# DragonShield.net
KiCad netlist of a schematic drawn in EAGLE
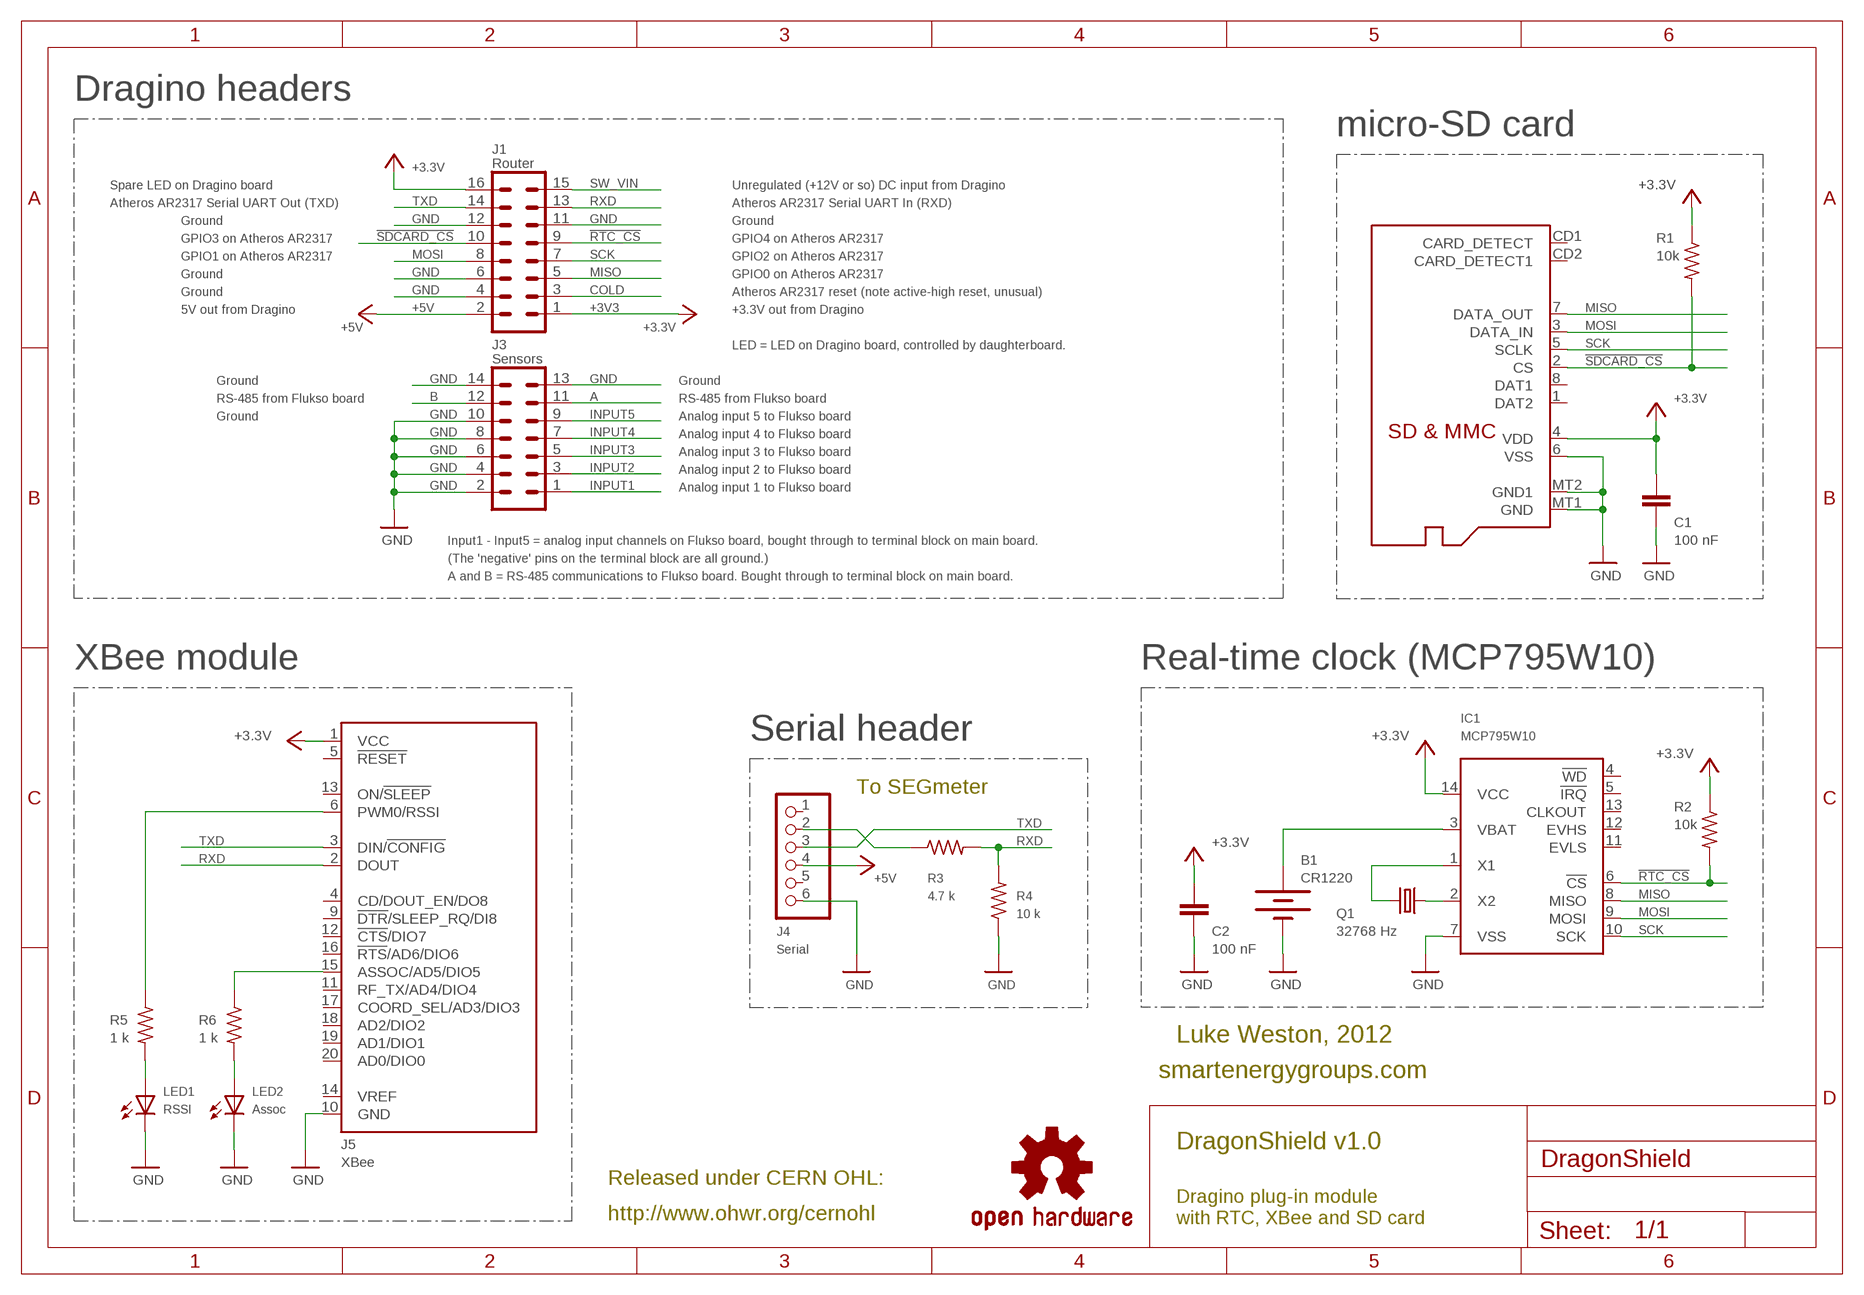
[diagram p0: schematic, sheet 1]

(export (version "E")
  (design (tool "Eeschema 10.0.6"))
  (components
    (comp (ref "B1")
      (value "CR1220")
      (footprint "eagle-import:BATTCON_12MM")
      (libsource (lib "eagle-import") (part "BATTERY12MM"))
    )
    (comp (ref "C1")
      (value "100 nF")
      (footprint "eagle-import:C0805K")
      (libsource (lib "eagle-import") (part "C-EUC0805K"))
    )
    (comp (ref "C2")
      (value "100 nF")
      (footprint "eagle-import:C0805K")
      (libsource (lib "eagle-import") (part "C-EUC0805K"))
    )
    (comp (ref "IC1")
      (value "MCP795W10")
      (footprint "eagle-import:SOIC14")
      (libsource (lib "eagle-import") (part "MCP795W10SO"))
    )
    (comp (ref "J1")
      (value "Router")
      (footprint "eagle-import:MA08-2")
      (libsource (lib "eagle-import") (part "MA08-2"))
    )
    (comp (ref "J2")
      (value "MICROSD")
      (footprint "eagle-import:MICROSD")
      (libsource (lib "eagle-import") (part "MICROSD"))
    )
    (comp (ref "J3")
      (value "Sensors")
      (footprint "eagle-import:MA07-2")
      (libsource (lib "eagle-import") (part "MA07-2"))
    )
    (comp (ref "J4")
      (value "Serial")
      (footprint "eagle-import:1X06")
      (libsource (lib "eagle-import") (part "PINHD-1X6"))
    )
    (comp (ref "J5")
      (value "XBee")
      (footprint "eagle-import:XBEE-PRO")
      (fields (field (name "MPN") "XBP24-AWI-001"))
      (libsource (lib "eagle-import") (part "XBEE-PRO"))
    )
    (comp (ref "LED1")
      (value "RSSI")
      (footprint "eagle-import:LED-0805-LARGE")
      (libsource (lib "eagle-import") (part "LED0805-LARGE"))
    )
    (comp (ref "LED2")
      (value "Assoc")
      (footprint "eagle-import:LED-0805-LARGE")
      (libsource (lib "eagle-import") (part "LED0805-LARGE"))
    )
    (comp (ref "Q1")
      (value "32768 Hz")
      (footprint "eagle-import:TC26H")
      (libsource (lib "eagle-import") (part "CRYSTALTC26H"))
    )
    (comp (ref "R1")
      (value "10k")
      (footprint "eagle-import:M0805")
      (libsource (lib "eagle-import") (part "R-US_M0805"))
    )
    (comp (ref "R2")
      (value "10k")
      (footprint "eagle-import:M0805")
      (libsource (lib "eagle-import") (part "R-US_M0805"))
    )
    (comp (ref "R3")
      (value "4.7 k")
      (footprint "eagle-import:M0805")
      (libsource (lib "eagle-import") (part "R-US_M0805"))
    )
    (comp (ref "R4")
      (value "10 k")
      (footprint "eagle-import:M0805")
      (libsource (lib "eagle-import") (part "R-US_M0805"))
    )
    (comp (ref "R5")
      (value "1 k")
      (footprint "eagle-import:M0805")
      (libsource (lib "eagle-import") (part "R-US_M0805"))
    )
    (comp (ref "R6")
      (value "1 k")
      (footprint "eagle-import:M0805")
      (libsource (lib "eagle-import") (part "R-US_M0805"))
    )
    (comp (ref "U$")
      (value "OSHW-LOGOS")
      (footprint "eagle-import:OSHW-LOGO-S")
      (libsource (lib "eagle-import") (part "OSHW-LOGOS"))
    )
  )
  (nets
    (net (code "1") (name "+3.3V") (class "Default")
      (node (ref "C1") (pin "2") (pinfunction "2_2") (pintype "passive"))
      (node (ref "C2") (pin "2") (pinfunction "2_2") (pintype "passive"))
      (node (ref "IC1") (pin "14") (pinfunction "VCC_14") (pintype "bidirectional"))
      (node (ref "J1") (pin "1") (pinfunction "1_1") (pintype "passive"))
      (node (ref "J1") (pin "16") (pinfunction "16_16") (pintype "passive"))
      (node (ref "J2") (pin "4") (pinfunction "VDD_4") (pintype "power_in"))
      (node (ref "J5") (pin "1") (pinfunction "VCC_1") (pintype "power_in"))
      (node (ref "R1") (pin "1") (pinfunction "1_1") (pintype "passive"))
      (node (ref "R2") (pin "1") (pinfunction "1_1") (pintype "passive"))
    )
    (net (code "2") (name "+5V") (class "Default")
      (node (ref "J1") (pin "2") (pinfunction "2_2") (pintype "passive"))
      (node (ref "J4") (pin "4") (pinfunction "4_4") (pintype "passive"))
    )
    (net (code "3") (name "/A") (class "Default")
      (node (ref "J3") (pin "11") (pinfunction "11_11") (pintype "passive"))
    )
    (net (code "4") (name "/B") (class "Default")
      (node (ref "J3") (pin "12") (pinfunction "12_12") (pintype "passive"))
    )
    (net (code "5") (name "/COLD") (class "Default")
      (node (ref "J1") (pin "3") (pinfunction "3_3") (pintype "passive"))
    )
    (net (code "6") (name "/INPUT1") (class "Default")
      (node (ref "J3") (pin "1") (pinfunction "1_1") (pintype "passive"))
    )
    (net (code "7") (name "/INPUT2") (class "Default")
      (node (ref "J3") (pin "3") (pinfunction "3_3") (pintype "passive"))
    )
    (net (code "8") (name "/INPUT3") (class "Default")
      (node (ref "J3") (pin "5") (pinfunction "5_5") (pintype "passive"))
    )
    (net (code "9") (name "/INPUT4") (class "Default")
      (node (ref "J3") (pin "7") (pinfunction "7_7") (pintype "passive"))
    )
    (net (code "10") (name "/INPUT5") (class "Default")
      (node (ref "J3") (pin "9") (pinfunction "9_9") (pintype "passive"))
    )
    (net (code "11") (name "/MISO") (class "Default")
      (node (ref "IC1") (pin "8") (pinfunction "MISO_8") (pintype "bidirectional"))
      (node (ref "J1") (pin "5") (pinfunction "5_5") (pintype "passive"))
      (node (ref "J2") (pin "7") (pinfunction "DATA_OUT_7") (pintype "output"))
    )
    (net (code "12") (name "/MOSI") (class "Default")
      (node (ref "IC1") (pin "9") (pinfunction "MOSI_9") (pintype "bidirectional"))
      (node (ref "J1") (pin "8") (pinfunction "8_8") (pintype "passive"))
      (node (ref "J2") (pin "3") (pinfunction "DATA_IN_3") (pintype "input"))
    )
    (net (code "13") (name "/RXD") (class "Default")
      (node (ref "J1") (pin "13") (pinfunction "13_13") (pintype "passive"))
      (node (ref "J5") (pin "2") (pinfunction "DOUT_2") (pintype "output"))
      (node (ref "R3") (pin "2") (pinfunction "2_2") (pintype "passive"))
      (node (ref "R4") (pin "2") (pinfunction "2_2") (pintype "passive"))
    )
    (net (code "14") (name "/SCK") (class "Default")
      (node (ref "IC1") (pin "10") (pinfunction "SCK_10") (pintype "bidirectional"))
      (node (ref "J1") (pin "7") (pinfunction "7_7") (pintype "passive"))
      (node (ref "J2") (pin "5") (pinfunction "SCLK_5") (pintype "input"))
    )
    (net (code "15") (name "/SW_VIN") (class "Default")
      (node (ref "J1") (pin "15") (pinfunction "15_15") (pintype "passive"))
    )
    (net (code "16") (name "/TXD") (class "Default")
      (node (ref "J1") (pin "14") (pinfunction "14_14") (pintype "passive"))
      (node (ref "J4") (pin "3") (pinfunction "3_3") (pintype "passive"))
      (node (ref "J5") (pin "3") (pinfunction "DIN/~{CONFIG}_3") (pintype "input"))
    )
    (net (code "17") (name "/~{RTC_CS}") (class "Default")
      (node (ref "IC1") (pin "6") (pinfunction "~{CS}_6") (pintype "bidirectional"))
      (node (ref "J1") (pin "9") (pinfunction "9_9") (pintype "passive"))
      (node (ref "R2") (pin "2") (pinfunction "2_2") (pintype "passive"))
    )
    (net (code "18") (name "/~{SDCARD_CS}") (class "Default")
      (node (ref "J1") (pin "10") (pinfunction "10_10") (pintype "passive"))
      (node (ref "J2") (pin "2") (pinfunction "CS_2") (pintype "input"))
      (node (ref "R1") (pin "2") (pinfunction "2_2") (pintype "passive"))
    )
    (net (code "19") (name "GND") (class "Default")
      (node (ref "B1") (pin "GND") (pinfunction "-_GND") (pintype "power_in"))
      (node (ref "C1") (pin "1") (pinfunction "1_1") (pintype "passive"))
      (node (ref "C2") (pin "1") (pinfunction "1_1") (pintype "passive"))
      (node (ref "IC1") (pin "7") (pinfunction "VSS_7") (pintype "bidirectional"))
      (node (ref "J1") (pin "11") (pinfunction "11_11") (pintype "passive"))
      (node (ref "J1") (pin "12") (pinfunction "12_12") (pintype "passive"))
      (node (ref "J1") (pin "4") (pinfunction "4_4") (pintype "passive"))
      (node (ref "J1") (pin "6") (pinfunction "6_6") (pintype "passive"))
      (node (ref "J2") (pin "6") (pinfunction "VSS_6") (pintype "power_in"))
      (node (ref "J2") (pin "MT1") (pinfunction "GND_MT1") (pintype "power_in"))
      (node (ref "J2") (pin "MT2") (pinfunction "GND1_MT2") (pintype "power_in"))
      (node (ref "J3") (pin "10") (pinfunction "10_10") (pintype "passive"))
      (node (ref "J3") (pin "13") (pinfunction "13_13") (pintype "passive"))
      (node (ref "J3") (pin "14") (pinfunction "14_14") (pintype "passive"))
      (node (ref "J3") (pin "2") (pinfunction "2_2") (pintype "passive"))
      (node (ref "J3") (pin "4") (pinfunction "4_4") (pintype "passive"))
      (node (ref "J3") (pin "6") (pinfunction "6_6") (pintype "passive"))
      (node (ref "J3") (pin "8") (pinfunction "8_8") (pintype "passive"))
      (node (ref "J4") (pin "6") (pinfunction "6_6") (pintype "passive"))
      (node (ref "J5") (pin "10") (pinfunction "GND_10") (pintype "power_in"))
      (node (ref "LED1") (pin "C") (pinfunction "C_C") (pintype "passive"))
      (node (ref "LED2") (pin "C") (pinfunction "C_C") (pintype "passive"))
      (node (ref "R4") (pin "1") (pinfunction "1_1") (pintype "passive"))
    )
    (net (code "20") (name "Net-(B1-+)") (class "Default")
      (node (ref "B1") (pin "PWR@1") (pinfunction "+_PWR@1") (pintype "power_in"))
      (node (ref "IC1") (pin "3") (pinfunction "VBAT_3") (pintype "bidirectional"))
    )
    (net (code "21") (name "Net-(IC1-X1)") (class "Default")
      (node (ref "IC1") (pin "1") (pinfunction "X1_1") (pintype "bidirectional"))
      (node (ref "Q1") (pin "2") (pinfunction "2_2") (pintype "passive"))
    )
    (net (code "22") (name "Net-(IC1-X2)") (class "Default")
      (node (ref "IC1") (pin "2") (pinfunction "X2_2") (pintype "bidirectional"))
      (node (ref "Q1") (pin "1") (pinfunction "1_1") (pintype "passive"))
    )
    (net (code "23") (name "Net-(J4-Pad2)") (class "Default")
      (node (ref "J4") (pin "2") (pinfunction "2_2") (pintype "passive"))
      (node (ref "R3") (pin "1") (pinfunction "1_1") (pintype "passive"))
    )
    (net (code "24") (name "Net-(J5-ASSOC{slash}AD5{slash}DIO5)") (class "Default")
      (node (ref "J5") (pin "15") (pinfunction "ASSOC/AD5/DIO5_15") (pintype "bidirectional"))
      (node (ref "R6") (pin "1") (pinfunction "1_1") (pintype "passive"))
    )
    (net (code "25") (name "Net-(J5-PWM0{slash}RSSI)") (class "Default")
      (node (ref "J5") (pin "6") (pinfunction "PWM0/RSSI_6") (pintype "output"))
      (node (ref "R5") (pin "1") (pinfunction "1_1") (pintype "passive"))
    )
    (net (code "26") (name "Net-(LED1-PadA)") (class "Default")
      (node (ref "LED1") (pin "A") (pinfunction "A_A") (pintype "passive"))
      (node (ref "R5") (pin "2") (pinfunction "2_2") (pintype "passive"))
    )
    (net (code "27") (name "Net-(LED2-PadA)") (class "Default")
      (node (ref "LED2") (pin "A") (pinfunction "A_A") (pintype "passive"))
      (node (ref "R6") (pin "2") (pinfunction "2_2") (pintype "passive"))
    )
    (net (code "28") (name "unconnected-(IC1-CLKOUT-Pad13)") (class "Default")
      (node (ref "IC1") (pin "13") (pinfunction "CLKOUT_13") (pintype "bidirectional"))
    )
    (net (code "29") (name "unconnected-(IC1-EVHS-Pad12)") (class "Default")
      (node (ref "IC1") (pin "12") (pinfunction "EVHS_12") (pintype "bidirectional"))
    )
    (net (code "30") (name "unconnected-(IC1-EVLS-Pad11)") (class "Default")
      (node (ref "IC1") (pin "11") (pinfunction "EVLS_11") (pintype "bidirectional"))
    )
    (net (code "31") (name "unconnected-(IC1-~{IRQ}-Pad5)") (class "Default")
      (node (ref "IC1") (pin "5") (pinfunction "~{IRQ}_5") (pintype "bidirectional"))
    )
    (net (code "32") (name "unconnected-(IC1-~{WD}-Pad4)") (class "Default")
      (node (ref "IC1") (pin "4") (pinfunction "~{WD}_4") (pintype "bidirectional"))
    )
    (net (code "33") (name "unconnected-(J2-CARD_DETECT-PadCD1)") (class "Default")
      (node (ref "J2") (pin "CD1") (pinfunction "CARD_DETECT_CD1") (pintype "passive"))
    )
    (net (code "34") (name "unconnected-(J2-CARD_DETECT1-PadCD2)") (class "Default")
      (node (ref "J2") (pin "CD2") (pinfunction "CARD_DETECT1_CD2") (pintype "passive"))
    )
    (net (code "35") (name "unconnected-(J2-DAT1-Pad8)") (class "Default")
      (node (ref "J2") (pin "8") (pinfunction "DAT1_8") (pintype "bidirectional"))
    )
    (net (code "36") (name "unconnected-(J2-DAT2-Pad1)") (class "Default")
      (node (ref "J2") (pin "1") (pinfunction "DAT2_1") (pintype "bidirectional"))
    )
    (net (code "37") (name "unconnected-(J4-Pad1)") (class "Default")
      (node (ref "J4") (pin "1") (pinfunction "1_1") (pintype "passive"))
    )
    (net (code "38") (name "unconnected-(J4-Pad5)") (class "Default")
      (node (ref "J4") (pin "5") (pinfunction "5_5") (pintype "passive"))
    )
    (net (code "39") (name "unconnected-(J5-AD0{slash}DIO0-Pad20)") (class "Default")
      (node (ref "J5") (pin "20") (pinfunction "AD0/DIO0_20") (pintype "bidirectional"))
    )
    (net (code "40") (name "unconnected-(J5-AD1{slash}DIO1-Pad19)") (class "Default")
      (node (ref "J5") (pin "19") (pinfunction "AD1/DIO1_19") (pintype "bidirectional"))
    )
    (net (code "41") (name "unconnected-(J5-AD2{slash}DIO2-Pad18)") (class "Default")
      (node (ref "J5") (pin "18") (pinfunction "AD2/DIO2_18") (pintype "bidirectional"))
    )
    (net (code "42") (name "unconnected-(J5-CD{slash}DOUT_EN{slash}DO8-Pad4)") (class "Default")
      (node (ref "J5") (pin "4") (pinfunction "CD/DOUT_EN/DO8_4") (pintype "output"))
    )
    (net (code "43") (name "unconnected-(J5-COORD_SEL{slash}AD3{slash}DIO3-Pad17)") (class "Default")
      (node (ref "J5") (pin "17") (pinfunction "COORD_SEL/AD3/DIO3_17") (pintype "bidirectional"))
    )
    (net (code "44") (name "unconnected-(J5-ON{slash}~{SLEEP}-Pad13)") (class "Default")
      (node (ref "J5") (pin "13") (pinfunction "ON/~{SLEEP}_13") (pintype "output"))
    )
    (net (code "45") (name "unconnected-(J5-RF_TX{slash}AD4{slash}DIO4-Pad11)") (class "Default")
      (node (ref "J5") (pin "11") (pinfunction "RF_TX/AD4/DIO4_11") (pintype "bidirectional"))
    )
    (net (code "46") (name "unconnected-(J5-VREF-Pad14)") (class "Default")
      (node (ref "J5") (pin "14") (pinfunction "VREF_14") (pintype "input"))
    )
    (net (code "47") (name "unconnected-(J5-~{CTS}{slash}DIO7-Pad12)") (class "Default")
      (node (ref "J5") (pin "12") (pinfunction "~{CTS}/DIO7_12") (pintype "bidirectional"))
    )
    (net (code "48") (name "unconnected-(J5-~{DTR}{slash}SLEEP_RQ{slash}DI8-Pad9)") (class "Default")
      (node (ref "J5") (pin "9") (pinfunction "~{DTR}/SLEEP_RQ/DI8_9") (pintype "bidirectional"))
    )
    (net (code "49") (name "unconnected-(J5-~{RESET}-Pad5)") (class "Default")
      (node (ref "J5") (pin "5") (pinfunction "~{RESET}_5") (pintype "input"))
    )
    (net (code "50") (name "unconnected-(J5-~{RTS}{slash}AD6{slash}DIO6-Pad16)") (class "Default")
      (node (ref "J5") (pin "16") (pinfunction "~{RTS}/AD6/DIO6_16") (pintype "bidirectional"))
    )
  )
)
